# USBC_Connector.net
KiCad netlist of a schematic drawn in Altium Designer
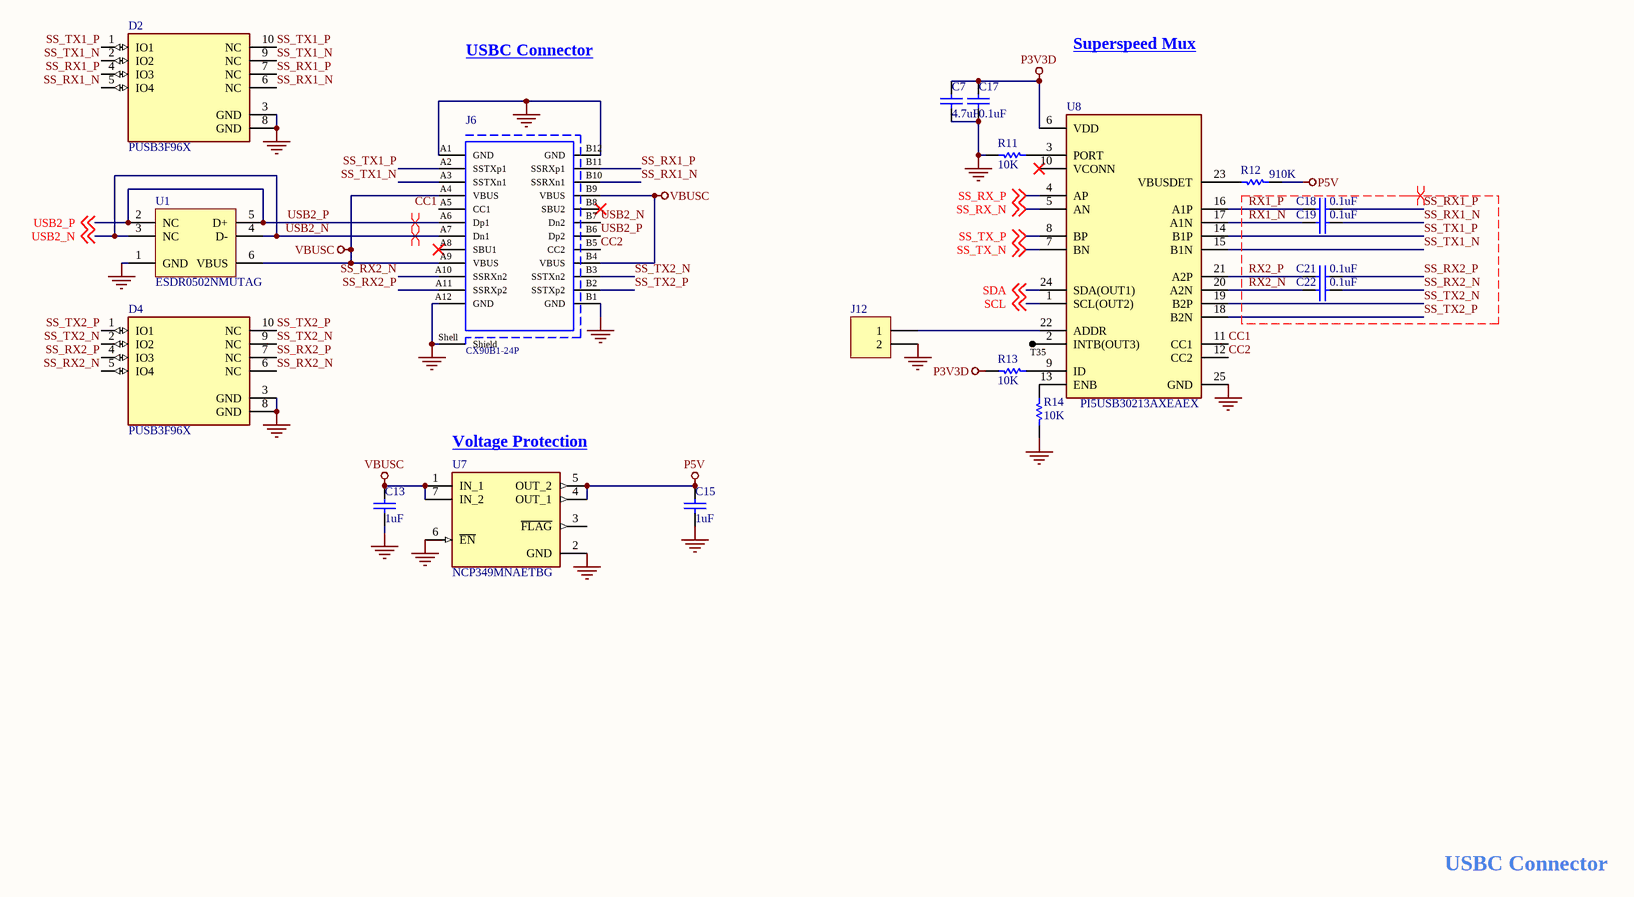
[diagram p0: USBC_Connector.SchDoc]

(export (version "E")
  (design (tool "Eeschema 10.0.6"))
  (components
    (comp (ref "C7")
      (value "4.7uF")
      (footprint "CAPC1005X55USR")
      (description "CAP CER 4.7UF 10V X5R 0402")
      (fields
        (field (name "MANUFACTURER PART NUMBER") "C1005X5R1A475M050BC")
        (field (name "MANUFACTURER") "TDK Corporation")
      )
      (libsource (lib "NX Module baseboard") (part "CAP CER 4.7UF 10V X5R 0402"))
    )
    (comp (ref "C13")
      (value "1uF")
      (footprint "CAPC1005X55USR")
      (description "CAP CER 1UF 25V X5R 0402")
      (fields
        (field (name "MANUFACTURER PART NUMBER") "GRM155R61E105MA12D")
        (field (name "MANUFACTURER") "Murata Electronics")
      )
      (libsource (lib "Tiger_Ti180") (part "CAP CER 1UF 25V X5R 0402"))
    )
    (comp (ref "C15")
      (value "1uF")
      (footprint "CAPC1005X55USR")
      (description "CAP CER 1UF 25V X5R 0402")
      (fields
        (field (name "MANUFACTURER PART NUMBER") "GRM155R61E105MA12D")
        (field (name "MANUFACTURER") "Murata Electronics")
      )
      (libsource (lib "Tiger_Ti180") (part "CAP CER 1UF 25V X5R 0402"))
    )
    (comp (ref "C17")
      (value "0.1uF")
      (footprint "CAPC1005X55USR")
      (description "CAP CER 0.1UF 16V X7R 0402")
      (fields
        (field (name "MANUFACTURER PART NUMBER") "CGA2B1X7R1C104K050BC")
        (field (name "MANUFACTURER") "TDK Corporation")
      )
      (libsource (lib "NX Module baseboard") (part "CAP CER 0.1UF 16V X7R 0402"))
    )
    (comp (ref "C18")
      (value "0.1uF")
      (footprint "CAPC1005X55USR")
      (description "CAP CER 0.1UF 16V X7R 0402")
      (fields
        (field (name "MANUFACTURER PART NUMBER") "CGA2B1X7R1C104K050BC")
        (field (name "MANUFACTURER") "TDK Corporation")
      )
      (libsource (lib "NX Module baseboard") (part "CAP CER 0.1UF 16V X7R 0402"))
    )
    (comp (ref "C19")
      (value "0.1uF")
      (footprint "CAPC1005X55USR")
      (description "CAP CER 0.1UF 16V X7R 0402")
      (fields
        (field (name "MANUFACTURER PART NUMBER") "CGA2B1X7R1C104K050BC")
        (field (name "MANUFACTURER") "TDK Corporation")
      )
      (libsource (lib "NX Module baseboard") (part "CAP CER 0.1UF 16V X7R 0402"))
    )
    (comp (ref "C21")
      (value "0.1uF")
      (footprint "CAPC1005X55USR")
      (description "CAP CER 0.1UF 16V X7R 0402")
      (fields
        (field (name "MANUFACTURER PART NUMBER") "CGA2B1X7R1C104K050BC")
        (field (name "MANUFACTURER") "TDK Corporation")
      )
      (libsource (lib "NX Module baseboard") (part "CAP CER 0.1UF 16V X7R 0402"))
    )
    (comp (ref "C22")
      (value "0.1uF")
      (footprint "CAPC1005X55USR")
      (description "CAP CER 0.1UF 16V X7R 0402")
      (fields
        (field (name "MANUFACTURER PART NUMBER") "CGA2B1X7R1C104K050BC")
        (field (name "MANUFACTURER") "TDK Corporation")
      )
      (libsource (lib "NX Module baseboard") (part "CAP CER 0.1UF 16V X7R 0402"))
    )
    (comp (ref "D2")
      (value "PUSB3F96X")
      (footprint "DFN2510A-10")
      (description "TVS DIODE 5.5VWM 4.6VC DFN2510A")
      (fields (field (name "MANUFACTURER") "Nexperia USA Inc."))
      (libsource (lib "Tiger_Ti180") (part "PUSB3F96X"))
    )
    (comp (ref "D4")
      (value "PUSB3F96X")
      (footprint "DFN2510A-10")
      (description "TVS DIODE 5.5VWM 4.6VC DFN2510A")
      (fields (field (name "MANUFACTURER") "Nexperia USA Inc."))
      (libsource (lib "Tiger_Ti180") (part "PUSB3F96X"))
    )
    (comp (ref "J6")
      (value "CX90B1-24P")
      (footprint "HRS_CX90B1-24P")
      (description "CONN RCP USB3.1 TYPEC 24P SMD RA")
      (fields (field (name "MANUFACTURER") "Hirose Electric Co Ltd"))
      (libsource (lib "Tiger_Ti180") (part "USB 3.1_HRS_CX90B1-24P"))
    )
    (comp (ref "J12")
      (value "Header 2X1_2.54MM")
      (footprint "HDR2X1_MALE_2.54MM")
      (description "CONN HEADER VERT 2POS 2.54MM")
      (fields
        (field (name "MANUFACTURER") "Wurth Electronics")
        (field (name "MANUFACTURER PART NUMBER") "61300211121")
      )
      (libsource (lib "NX Module baseboard") (part "Header 2X1_2.54MM"))
    )
    (comp (ref "R11")
      (value "10K")
      (footprint "RESC1005X40USR")
      (description "RES SMD 10K OHM 1% 1/16W 0402")
      (fields
        (field (name "MANUFACTURER") "Samsung Electro-Mechanics")
        (field (name "MANUFACTURER PART NUMBER") "RC1005F103CS")
      )
      (libsource (lib "NX Module baseboard") (part "RES SMD 10K OHM 1% 1/16W 0402"))
    )
    (comp (ref "R12")
      (value "910K")
      (footprint "RESC1005X40USR")
      (description "RES 910K OHM 1% 1/16W 0402")
      (fields
        (field (name "MANUFACTURER") "YAGEO")
        (field (name "MANUFACTURER PART NUMBER") "RC0402FR-07910KL")
      )
      (libsource (lib "NX Module baseboard") (part "RES 910K OHM 1% 1/16W 0402"))
    )
    (comp (ref "R13")
      (value "10K")
      (footprint "RESC1005X40USR")
      (description "RES SMD 10K OHM 1% 1/16W 0402")
      (fields
        (field (name "MANUFACTURER") "Samsung Electro-Mechanics")
        (field (name "MANUFACTURER PART NUMBER") "RC1005F103CS")
      )
      (libsource (lib "NX Module baseboard") (part "RES SMD 10K OHM 1% 1/16W 0402"))
    )
    (comp (ref "R14")
      (value "10K")
      (footprint "RESC1005X40USR")
      (description "RES SMD 10K OHM 1% 1/16W 0402")
      (fields
        (field (name "MANUFACTURER") "Samsung Electro-Mechanics")
        (field (name "MANUFACTURER PART NUMBER") "RC1005F103CS")
      )
      (libsource (lib "NX Module baseboard") (part "RES SMD 10K OHM 1% 1/16W 0402"))
    )
    (comp (ref "T35")
      (value "TP_S")
      (footprint "TP 20mil")
      (description "test point")
      (libsource (lib "AiC RVP Adapter") (part "TP_S"))
    )
    (comp (ref "U1")
      (value "ESDR0502NMUTAG")
      (footprint "ONSC-UDFN-6-517AA-01_V")
      (description "TVS DIODE 5.5VWM 6UDFN")
      (fields (field (name "MANUFACTURER") "ON Semiconductor"))
      (libsource (lib "Tiger_Ti180") (part "ONSC-ESDR0502N-UDFN-6-517AA-01"))
    )
    (comp (ref "U7")
      (value "NCP349MNAETBG")
      (footprint "SON50P200X160X100-7N-D")
      (description "IC CTLR OVP 28V W/NMOS 6-DFN")
      (fields (field (name "MANUFACTURER") "ON Semiconductor"))
      (libsource (lib "Tiger_Ti180") (part "NCP349MNAETBG"))
    )
    (comp (ref "U8")
      (value "PI5USB30213AXEAEX")
      (footprint "QFN40P400X200X50-25N")
      (description "USB Power SW DIST Single 2.7V to 5.5V 1.5A/3A 24-Pin TQFN T/R")
      (fields
        (field (name "MANUFACTURER") "Diodes")
        (field (name "MANUFACTURER PART NUMBER") "PI5USB30213XEAEX")
      )
      (libsource (lib "NX Module baseboard") (part "PI5USB30213XEAEX"))
    )
  )
  (nets
    (net (code "1") (name "/CC1") (class "Default")
      (node (ref "J6") (pin "A5") (pinfunction "CC1_A5") (pintype "passive"))
      (node (ref "U8") (pin "11") (pinfunction "CC1_11") (pintype "passive"))
    )
    (net (code "2") (name "/CC2") (class "Default")
      (node (ref "J6") (pin "B5") (pinfunction "CC2_B5") (pintype "passive"))
      (node (ref "U8") (pin "12") (pinfunction "CC2_12") (pintype "passive"))
    )
    (net (code "3") (name "/RX1_N") (class "Default")
      (node (ref "C19") (pin "1") (pinfunction "1_1") (pintype "passive"))
      (node (ref "U8") (pin "17") (pinfunction "A1N_17") (pintype "passive"))
    )
    (net (code "4") (name "/RX1_P") (class "Default")
      (node (ref "C18") (pin "1") (pinfunction "1_1") (pintype "passive"))
      (node (ref "U8") (pin "16") (pinfunction "A1P_16") (pintype "passive"))
    )
    (net (code "5") (name "/RX2_N") (class "Default")
      (node (ref "C22") (pin "1") (pinfunction "1_1") (pintype "passive"))
      (node (ref "U8") (pin "20") (pinfunction "A2N_20") (pintype "passive"))
    )
    (net (code "6") (name "/RX2_P") (class "Default")
      (node (ref "C21") (pin "1") (pinfunction "1_1") (pintype "passive"))
      (node (ref "U8") (pin "21") (pinfunction "A2P_21") (pintype "passive"))
    )
    (net (code "7") (name "/SS_RX1_N") (class "Default")
      (node (ref "C19") (pin "2") (pinfunction "2_2") (pintype "passive"))
      (node (ref "D2") (pin "5") (pinfunction "IO4_5") (pintype "bidirectional"))
      (node (ref "D2") (pin "6") (pinfunction "NC_6") (pintype "passive"))
      (node (ref "J6") (pin "B10") (pinfunction "SSRXn1_B10") (pintype "passive"))
    )
    (net (code "8") (name "/SS_RX1_P") (class "Default")
      (node (ref "C18") (pin "2") (pinfunction "2_2") (pintype "passive"))
      (node (ref "D2") (pin "4") (pinfunction "IO3_4") (pintype "bidirectional"))
      (node (ref "D2") (pin "7") (pinfunction "NC_7") (pintype "passive"))
      (node (ref "J6") (pin "B11") (pinfunction "SSRXp1_B11") (pintype "passive"))
    )
    (net (code "9") (name "/SS_RX2_N") (class "Default")
      (node (ref "C22") (pin "2") (pinfunction "2_2") (pintype "passive"))
      (node (ref "D4") (pin "5") (pinfunction "IO4_5") (pintype "bidirectional"))
      (node (ref "D4") (pin "6") (pinfunction "NC_6") (pintype "passive"))
      (node (ref "J6") (pin "A10") (pinfunction "SSRXn2_A10") (pintype "passive"))
    )
    (net (code "10") (name "/SS_RX2_P") (class "Default")
      (node (ref "C21") (pin "2") (pinfunction "2_2") (pintype "passive"))
      (node (ref "D4") (pin "4") (pinfunction "IO3_4") (pintype "bidirectional"))
      (node (ref "D4") (pin "7") (pinfunction "NC_7") (pintype "passive"))
      (node (ref "J6") (pin "A11") (pinfunction "SSRXp2_A11") (pintype "passive"))
    )
    (net (code "11") (name "/SS_TX1_N") (class "Default")
      (node (ref "D2") (pin "2") (pinfunction "IO2_2") (pintype "bidirectional"))
      (node (ref "D2") (pin "9") (pinfunction "NC_9") (pintype "passive"))
      (node (ref "J6") (pin "A3") (pinfunction "SSTXn1_A3") (pintype "passive"))
      (node (ref "U8") (pin "15") (pinfunction "B1N_15") (pintype "passive"))
    )
    (net (code "12") (name "/SS_TX1_P") (class "Default")
      (node (ref "D2") (pin "1") (pinfunction "IO1_1") (pintype "bidirectional"))
      (node (ref "D2") (pin "10") (pinfunction "NC_10") (pintype "passive"))
      (node (ref "J6") (pin "A2") (pinfunction "SSTXp1_A2") (pintype "passive"))
      (node (ref "U8") (pin "14") (pinfunction "B1P_14") (pintype "passive"))
    )
    (net (code "13") (name "/SS_TX2_N") (class "Default")
      (node (ref "D4") (pin "2") (pinfunction "IO2_2") (pintype "bidirectional"))
      (node (ref "D4") (pin "9") (pinfunction "NC_9") (pintype "passive"))
      (node (ref "J6") (pin "B3") (pinfunction "SSTXn2_B3") (pintype "passive"))
      (node (ref "U8") (pin "19") (pinfunction "B2P_19") (pintype "passive"))
    )
    (net (code "14") (name "/SS_TX2_P") (class "Default")
      (node (ref "D4") (pin "1") (pinfunction "IO1_1") (pintype "bidirectional"))
      (node (ref "D4") (pin "10") (pinfunction "NC_10") (pintype "passive"))
      (node (ref "J6") (pin "B2") (pinfunction "SSTXp2_B2") (pintype "passive"))
      (node (ref "U8") (pin "18") (pinfunction "B2N_18") (pintype "passive"))
    )
    (net (code "15") (name "GND") (class "Default")
      (node (ref "C13") (pin "1") (pinfunction "1_1") (pintype "passive"))
      (node (ref "C15") (pin "1") (pinfunction "1_1") (pintype "passive"))
      (node (ref "C17") (pin "1") (pinfunction "1_1") (pintype "passive"))
      (node (ref "C7") (pin "1") (pinfunction "1_1") (pintype "passive"))
      (node (ref "D2") (pin "3") (pinfunction "GND_3") (pintype "power_in"))
      (node (ref "D2") (pin "8") (pinfunction "GND_8") (pintype "power_in"))
      (node (ref "D4") (pin "3") (pinfunction "GND_3") (pintype "power_in"))
      (node (ref "D4") (pin "8") (pinfunction "GND_8") (pintype "power_in"))
      (node (ref "J12") (pin "2") (pinfunction "2_2") (pintype "passive"))
      (node (ref "J6") (pin "A1") (pinfunction "GND_A1") (pintype "passive"))
      (node (ref "J6") (pin "A12") (pinfunction "GND_A12") (pintype "passive"))
      (node (ref "J6") (pin "B1") (pinfunction "GND_B1") (pintype "passive"))
      (node (ref "J6") (pin "B12") (pinfunction "GND_B12") (pintype "passive"))
      (node (ref "J6") (pin "Shell") (pinfunction "Shield_Shell") (pintype "passive"))
      (node (ref "R11") (pin "1") (pinfunction "1_1") (pintype "passive"))
      (node (ref "R14") (pin "2") (pinfunction "2_2") (pintype "passive"))
      (node (ref "U1") (pin "1") (pinfunction "GND_1") (pintype "power_in"))
      (node (ref "U7") (pin "2") (pinfunction "GND_2") (pintype "power_in"))
      (node (ref "U7") (pin "6") (pinfunction "~{EN}_6") (pintype "input"))
      (node (ref "U8") (pin "25") (pinfunction "GND_25") (pintype "passive"))
    )
    (net (code "16") (name "Net-(U8-ADDR)") (class "Default")
      (node (ref "J12") (pin "1") (pinfunction "1_1") (pintype "passive"))
      (node (ref "U8") (pin "22") (pinfunction "ADDR_22") (pintype "passive"))
    )
    (net (code "17") (name "Net-(U8-ENB)") (class "Default")
      (node (ref "R14") (pin "1") (pinfunction "1_1") (pintype "passive"))
      (node (ref "U8") (pin "13") (pinfunction "ENB_13") (pintype "passive"))
    )
    (net (code "18") (name "Net-(U8-ID)") (class "Default")
      (node (ref "R13") (pin "2") (pinfunction "2_2") (pintype "passive"))
      (node (ref "U8") (pin "9") (pinfunction "ID_9") (pintype "passive"))
    )
    (net (code "19") (name "Net-(U8-INTB(OUT3))") (class "Default")
      (node (ref "T35") (pin "1") (pintype "passive"))
      (node (ref "U8") (pin "2") (pinfunction "INTB(OUT3)_2") (pintype "passive"))
    )
    (net (code "20") (name "Net-(U8-PORT)") (class "Default")
      (node (ref "R11") (pin "2") (pinfunction "2_2") (pintype "passive"))
      (node (ref "U8") (pin "3") (pinfunction "PORT_3") (pintype "passive"))
    )
    (net (code "21") (name "Net-(U8-VBUSDET)") (class "Default")
      (node (ref "R12") (pin "1") (pinfunction "1_1") (pintype "passive"))
      (node (ref "U8") (pin "23") (pinfunction "VBUSDET_23") (pintype "passive"))
    )
    (net (code "22") (name "P3V3D") (class "Default")
      (node (ref "C17") (pin "2") (pinfunction "2_2") (pintype "passive"))
      (node (ref "C7") (pin "2") (pinfunction "2_2") (pintype "passive"))
      (node (ref "R13") (pin "1") (pinfunction "1_1") (pintype "passive"))
      (node (ref "U8") (pin "6") (pinfunction "VDD_6") (pintype "passive"))
    )
    (net (code "23") (name "P5V") (class "Default")
      (node (ref "C15") (pin "2") (pinfunction "2_2") (pintype "passive"))
      (node (ref "R12") (pin "2") (pinfunction "2_2") (pintype "passive"))
      (node (ref "U7") (pin "4") (pinfunction "OUT_1_4") (pintype "output"))
      (node (ref "U7") (pin "5") (pinfunction "OUT_2_5") (pintype "output"))
    )
    (net (code "24") (name "SCL") (class "Default")
      (node (ref "U8") (pin "1") (pinfunction "SCL(OUT2)_1") (pintype "passive"))
    )
    (net (code "25") (name "SDA") (class "Default")
      (node (ref "U8") (pin "24") (pinfunction "SDA(OUT1)_24") (pintype "passive"))
    )
    (net (code "26") (name "SS_RX_N") (class "Default")
      (node (ref "U8") (pin "5") (pinfunction "AN_5") (pintype "passive"))
    )
    (net (code "27") (name "SS_RX_P") (class "Default")
      (node (ref "U8") (pin "4") (pinfunction "AP_4") (pintype "passive"))
    )
    (net (code "28") (name "SS_TX_N") (class "Default")
      (node (ref "U8") (pin "7") (pinfunction "BN_7") (pintype "passive"))
    )
    (net (code "29") (name "SS_TX_P") (class "Default")
      (node (ref "U8") (pin "8") (pinfunction "BP_8") (pintype "passive"))
    )
    (net (code "30") (name "USB2_N") (class "Default")
      (node (ref "J6") (pin "A7") (pinfunction "Dn1_A7") (pintype "passive"))
      (node (ref "J6") (pin "B7") (pinfunction "Dn2_B7") (pintype "passive"))
      (node (ref "U1") (pin "3") (pinfunction "NC_3") (pintype "passive"))
      (node (ref "U1") (pin "4") (pinfunction "D-_4") (pintype "passive"))
    )
    (net (code "31") (name "USB2_P") (class "Default")
      (node (ref "J6") (pin "A6") (pinfunction "Dp1_A6") (pintype "passive"))
      (node (ref "J6") (pin "B6") (pinfunction "Dp2_B6") (pintype "passive"))
      (node (ref "U1") (pin "2") (pinfunction "NC_2") (pintype "passive"))
      (node (ref "U1") (pin "5") (pinfunction "D+_5") (pintype "passive"))
    )
    (net (code "32") (name "VBUSC") (class "Default")
      (node (ref "C13") (pin "2") (pinfunction "2_2") (pintype "passive"))
      (node (ref "J6") (pin "A4") (pinfunction "VBUS_A4") (pintype "passive"))
      (node (ref "J6") (pin "A9") (pinfunction "VBUS_A9") (pintype "passive"))
      (node (ref "J6") (pin "B4") (pinfunction "VBUS_B4") (pintype "passive"))
      (node (ref "J6") (pin "B9") (pinfunction "VBUS_B9") (pintype "passive"))
      (node (ref "U1") (pin "6") (pinfunction "VBUS_6") (pintype "power_in"))
      (node (ref "U7") (pin "1") (pinfunction "IN_1_1") (pintype "power_in"))
      (node (ref "U7") (pin "7") (pinfunction "IN_2_7") (pintype "power_in"))
    )
    (net (code "33") (name "unconnected-(J6-SBU1-PadA8)") (class "Default")
      (node (ref "J6") (pin "A8") (pinfunction "SBU1_A8") (pintype "passive+no_connect"))
    )
    (net (code "34") (name "unconnected-(J6-SBU2-PadB8)") (class "Default")
      (node (ref "J6") (pin "B8") (pinfunction "SBU2_B8") (pintype "passive+no_connect"))
    )
    (net (code "35") (name "unconnected-(U7-~{FLAG}-Pad3)") (class "Default")
      (node (ref "U7") (pin "3") (pinfunction "~{FLAG}_3") (pintype "output"))
    )
    (net (code "36") (name "unconnected-(U8-VCONN-Pad10)") (class "Default")
      (node (ref "U8") (pin "10") (pinfunction "VCONN_10") (pintype "passive+no_connect"))
    )
  )
)
